# receiver.net
KiCad netlist of a schematic drawn in Altium Designer
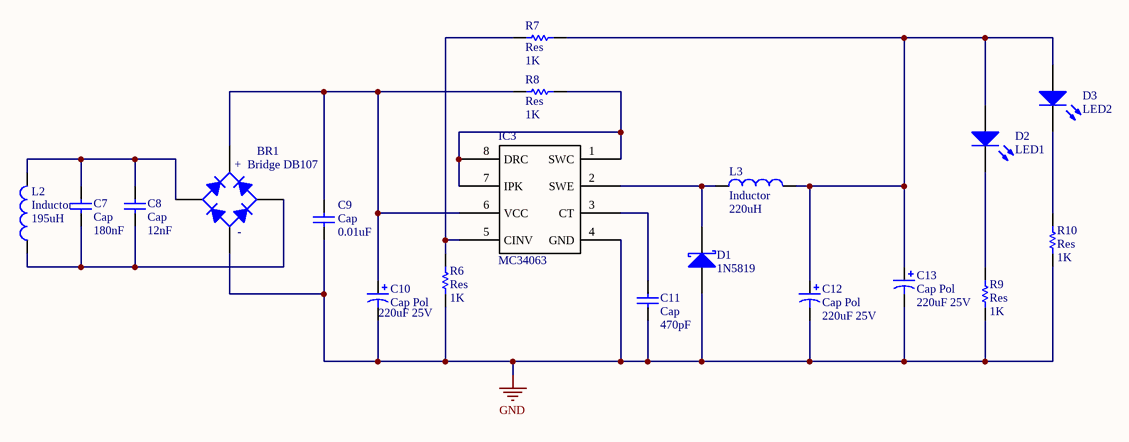
[diagram p0: receiver.SchDoc]

(export (version "E")
  (design (tool "Eeschema 10.0.6"))
  (components
    (comp (ref "BR1")
      (value "Bridge DB107")
      (footprint "D-38")
      (description "Full Wave Diode Bridge")
      (fields (field (name "PUBLISHER") "Altium Limited"))
      (libsource (lib "Miscellaneous Devices") (part "Bridge1"))
    )
    (comp (ref "C7")
      (value "Cap")
      (footprint "RAD-0.3")
      (description "Capacitor")
      (fields (field (name "ALTIUM_VALUE") "180nF") (field (name "PUBLISHER") "Altium Limited"))
      (libsource (lib "Miscellaneous Devices") (part "Cap"))
    )
    (comp (ref "C8")
      (value "Cap")
      (footprint "RAD-0.3")
      (description "Capacitor")
      (fields (field (name "ALTIUM_VALUE") "12nF") (field (name "PUBLISHER") "Altium Limited"))
      (libsource (lib "Miscellaneous Devices") (part "Cap"))
    )
    (comp (ref "C9")
      (value "Cap")
      (footprint "RAD-0.3")
      (description "Capacitor")
      (fields (field (name "ALTIUM_VALUE") "0.01uF") (field (name "PUBLISHER") "Altium Limited"))
      (libsource (lib "Miscellaneous Devices") (part "Cap"))
    )
    (comp (ref "C10")
      (value "Cap Pol")
      (footprint "RB7.6-15")
      (description "Polarized Capacitor (Radial)")
      (fields (field (name "ALTIUM_VALUE") "220uF 25V") (field (name "PUBLISHER") "Altium Limited"))
      (libsource (lib "Miscellaneous Devices") (part "Cap Pol1"))
    )
    (comp (ref "C11")
      (value "Cap")
      (footprint "RAD-0.3")
      (description "Capacitor")
      (fields (field (name "ALTIUM_VALUE") "470pF") (field (name "PUBLISHER") "Altium Limited"))
      (libsource (lib "Miscellaneous Devices") (part "Cap"))
    )
    (comp (ref "C12")
      (value "Cap Pol")
      (footprint "RB7.6-15")
      (description "Polarized Capacitor (Radial)")
      (fields (field (name "ALTIUM_VALUE") "220uF 25V") (field (name "PUBLISHER") "Altium Limited"))
      (libsource (lib "Miscellaneous Devices") (part "Cap Pol1"))
    )
    (comp (ref "C13")
      (value "Cap Pol")
      (footprint "RB7.6-15")
      (description "Polarized Capacitor (Radial)")
      (fields (field (name "ALTIUM_VALUE") "220uF 25V") (field (name "PUBLISHER") "Altium Limited"))
      (libsource (lib "Miscellaneous Devices") (part "Cap Pol1"))
    )
    (comp (ref "D1")
      (value "1N5819")
      (footprint "DIODE-0.4")
      (description "Schottky Rectifier")
      (fields (field (name "PUBLISHER") "Altium Limited"))
      (libsource (lib "Miscellaneous Devices") (part "Diode 10TQ035"))
    )
    (comp (ref "D2")
      (value "LED1")
      (footprint "LED-0")
      (description "Typical INFRARED GaAs LED")
      (fields (field (name "PUBLISHER") "Altium Limited"))
      (libsource (lib "Miscellaneous Devices") (part "LED0"))
    )
    (comp (ref "D3")
      (value "LED2")
      (footprint "LED-0")
      (description "Typical INFRARED GaAs LED")
      (fields (field (name "PUBLISHER") "Altium Limited"))
      (libsource (lib "Miscellaneous Devices") (part "LED0"))
    )
    (comp (ref "IC3") (value "MC34063") (footprint "PDIP-8") (libsource (lib "MC34063") (part "MC34063")))
    (comp (ref "L2")
      (value "Inductor")
      (footprint "HDR1X2")
      (fields (field (name "ALTIUM_VALUE") "195uH") (field (name "PUBLISHER") "Altium Limited"))
      (libsource (lib "Miscellaneous Devices") (part "Inductor"))
    )
    (comp (ref "L3")
      (value "Inductor")
      (footprint "AXIAL-0.4")
      (fields (field (name "ALTIUM_VALUE") "220uH") (field (name "PUBLISHER") "Altium Limited"))
      (libsource (lib "Miscellaneous Devices") (part "Inductor"))
    )
    (comp (ref "R6")
      (value "Res")
      (footprint "AXIAL-0.3")
      (description "Resistor")
      (fields (field (name "ALTIUM_VALUE") "1K") (field (name "PUBLISHER") "Altium Limited"))
      (libsource (lib "Miscellaneous Devices") (part "Res1"))
    )
    (comp (ref "R7")
      (value "Res")
      (footprint "AXIAL-0.3")
      (description "Resistor")
      (fields (field (name "ALTIUM_VALUE") "1K") (field (name "PUBLISHER") "Altium Limited"))
      (libsource (lib "Miscellaneous Devices") (part "Res1"))
    )
    (comp (ref "R8")
      (value "Res")
      (footprint "AXIAL-0.3")
      (description "Resistor")
      (fields (field (name "ALTIUM_VALUE") "1K") (field (name "PUBLISHER") "Altium Limited"))
      (libsource (lib "Miscellaneous Devices") (part "Res1"))
    )
    (comp (ref "R9")
      (value "Res")
      (footprint "AXIAL-0.3")
      (description "Resistor")
      (fields (field (name "ALTIUM_VALUE") "1K") (field (name "PUBLISHER") "Altium Limited"))
      (libsource (lib "Miscellaneous Devices") (part "Res1"))
    )
    (comp (ref "R10")
      (value "Res")
      (footprint "AXIAL-0.3")
      (description "Resistor")
      (fields (field (name "ALTIUM_VALUE") "1K") (field (name "PUBLISHER") "Altium Limited"))
      (libsource (lib "Miscellaneous Devices") (part "Res1"))
    )
  )
  (nets
    (net (code "1") (name "GND") (class "Default")
      (node (ref "BR1") (pin "3") (pinfunction "A_3") (pintype "passive"))
      (node (ref "C10") (pin "2") (pinfunction "2_2") (pintype "passive"))
      (node (ref "C11") (pin "1") (pinfunction "1_1") (pintype "passive"))
      (node (ref "C12") (pin "2") (pinfunction "2_2") (pintype "passive"))
      (node (ref "C13") (pin "2") (pinfunction "2_2") (pintype "passive"))
      (node (ref "C9") (pin "1") (pinfunction "1_1") (pintype "passive"))
      (node (ref "D1") (pin "2") (pinfunction "A_2") (pintype "passive"))
      (node (ref "IC3") (pin "4") (pinfunction "GND_4") (pintype "passive"))
      (node (ref "R10") (pin "2") (pinfunction "2_2") (pintype "passive"))
      (node (ref "R6") (pin "1") (pinfunction "1_1") (pintype "passive"))
      (node (ref "R9") (pin "2") (pinfunction "2_2") (pintype "passive"))
    )
    (net (code "2") (name "Net-(BR1-C-Pad2)") (class "Default")
      (node (ref "BR1") (pin "2") (pinfunction "C_2") (pintype "passive"))
      (node (ref "C7") (pin "1") (pinfunction "1_1") (pintype "passive"))
      (node (ref "C8") (pin "1") (pinfunction "1_1") (pintype "passive"))
      (node (ref "L2") (pin "1") (pinfunction "1_1") (pintype "passive"))
    )
    (net (code "3") (name "Net-(BR1-C-Pad4)") (class "Default")
      (node (ref "BR1") (pin "4") (pinfunction "C_4") (pintype "passive"))
      (node (ref "C7") (pin "2") (pinfunction "2_2") (pintype "passive"))
      (node (ref "C8") (pin "2") (pinfunction "2_2") (pintype "passive"))
      (node (ref "L2") (pin "2") (pinfunction "2_2") (pintype "passive"))
    )
    (net (code "4") (name "Net-(BR1-K)") (class "Default")
      (node (ref "BR1") (pin "1") (pinfunction "K_1") (pintype "passive"))
      (node (ref "C10") (pin "1") (pinfunction "1_1") (pintype "passive"))
      (node (ref "C9") (pin "2") (pinfunction "2_2") (pintype "passive"))
      (node (ref "IC3") (pin "6") (pinfunction "VCC_6") (pintype "passive"))
      (node (ref "R8") (pin "2") (pinfunction "2_2") (pintype "passive"))
    )
    (net (code "5") (name "Net-(D1-K)") (class "Default")
      (node (ref "D1") (pin "1") (pinfunction "K_1") (pintype "passive"))
      (node (ref "IC3") (pin "2") (pinfunction "SWE_2") (pintype "passive"))
      (node (ref "L3") (pin "1") (pinfunction "1_1") (pintype "passive"))
    )
    (net (code "6") (name "Net-(D2-A)") (class "Default")
      (node (ref "C12") (pin "1") (pinfunction "1_1") (pintype "passive"))
      (node (ref "C13") (pin "1") (pinfunction "1_1") (pintype "passive"))
      (node (ref "D2") (pin "1") (pinfunction "A_1") (pintype "passive"))
      (node (ref "D3") (pin "1") (pinfunction "A_1") (pintype "passive"))
      (node (ref "L3") (pin "2") (pinfunction "2_2") (pintype "passive"))
      (node (ref "R7") (pin "1") (pinfunction "1_1") (pintype "passive"))
    )
    (net (code "7") (name "Net-(D2-K)") (class "Default")
      (node (ref "D2") (pin "2") (pinfunction "K_2") (pintype "passive"))
      (node (ref "R9") (pin "1") (pinfunction "1_1") (pintype "passive"))
    )
    (net (code "8") (name "Net-(D3-K)") (class "Default")
      (node (ref "D3") (pin "2") (pinfunction "K_2") (pintype "passive"))
      (node (ref "R10") (pin "1") (pinfunction "1_1") (pintype "passive"))
    )
    (net (code "9") (name "Net-(IC3-CINV)") (class "Default")
      (node (ref "IC3") (pin "5") (pinfunction "CINV_5") (pintype "passive"))
      (node (ref "R6") (pin "2") (pinfunction "2_2") (pintype "passive"))
      (node (ref "R7") (pin "2") (pinfunction "2_2") (pintype "passive"))
    )
    (net (code "10") (name "Net-(IC3-CT)") (class "Default")
      (node (ref "C11") (pin "2") (pinfunction "2_2") (pintype "passive"))
      (node (ref "IC3") (pin "3") (pinfunction "CT_3") (pintype "passive"))
    )
    (net (code "11") (name "Net-(IC3-DRC)") (class "Default")
      (node (ref "IC3") (pin "1") (pinfunction "SWC_1") (pintype "passive"))
      (node (ref "IC3") (pin "7") (pinfunction "IPK_7") (pintype "passive"))
      (node (ref "IC3") (pin "8") (pinfunction "DRC_8") (pintype "passive"))
      (node (ref "R8") (pin "1") (pinfunction "1_1") (pintype "passive"))
    )
  )
)
